# ssr_ansteuerung_v7.net
KiCad netlist of a schematic drawn in EAGLE
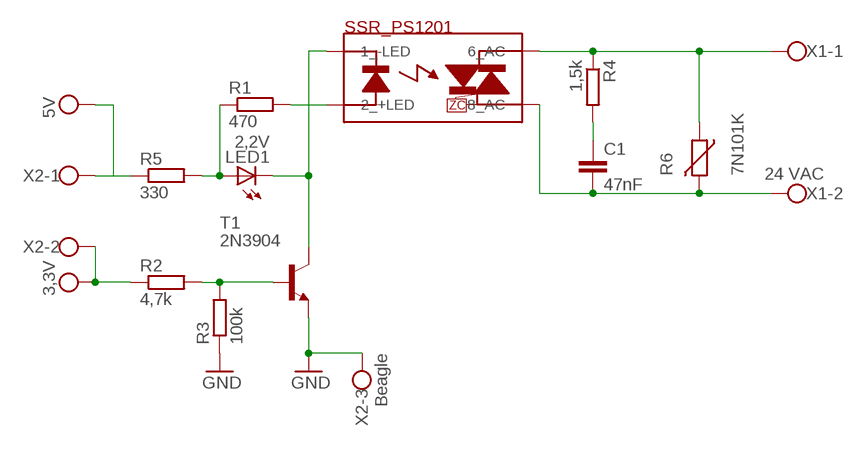
[diagram p0: schematic, sheet 1]

(export (version "E")
  (design (tool "Eeschema 10.0.6"))
  (components
    (comp (ref "C1")
      (value "47nF")
      (footprint "eagle-import:C7.5B3")
      (libsource (lib "eagle-import") (part "C7.5/3"))
    )
    (comp (ref "LED1")
      (value "2,2V")
      (footprint "eagle-import:LED5MM")
      (libsource (lib "eagle-import") (part "LED5MM"))
    )
    (comp (ref "R1")
      (value "470")
      (footprint "eagle-import:0204_7")
      (libsource (lib "eagle-import") (part "R-EU_0204/7"))
    )
    (comp (ref "R2")
      (value "4,7k")
      (footprint "eagle-import:0204_7")
      (libsource (lib "eagle-import") (part "R-EU_0204/7"))
    )
    (comp (ref "R3")
      (value "100k")
      (footprint "eagle-import:0204_7")
      (libsource (lib "eagle-import") (part "R-EU_0204/7"))
    )
    (comp (ref "R4")
      (value "1,5k")
      (footprint "eagle-import:0204_7")
      (libsource (lib "eagle-import") (part "R-EU_0204/7"))
    )
    (comp (ref "R5")
      (value "330")
      (footprint "eagle-import:0204_7")
      (libsource (lib "eagle-import") (part "R-EU_0204/7"))
    )
    (comp (ref "R6")
      (value "7N101K")
      (footprint "eagle-import:R-5")
      (libsource (lib "eagle-import") (part "VARISTOR-5"))
    )
    (comp (ref "SSR_PS1201")
      (value "SSR PS1201")
      (footprint "eagle-import:S202S02")
      (libsource (lib "eagle-import") (part "IXYS_PS1201_SSRSIP4/8"))
    )
    (comp (ref "T1")
      (value "2N3904")
      (footprint "eagle-import:TO92")
      (libsource (lib "eagle-import") (part "2N3904"))
    )
    (comp (ref "X1")
      (value "24 VAC")
      (footprint "eagle-import:W237-102")
      (fields (field (name "MPN") "237-102"))
      (libsource (lib "eagle-import") (part "W237-102"))
    )
    (comp (ref "X2")
      (value "Beagle")
      (footprint "eagle-import:W237-103")
      (fields (field (name "MPN") "237-103"))
      (libsource (lib "eagle-import") (part "W237-103"))
    )
  )
  (nets
    (net (code "1") (name "3,3V") (class "Default")
      (node (ref "R2") (pin "1") (pinfunction "1_1") (pintype "passive"))
      (node (ref "X2") (pin "2") (pinfunction "KL_2") (pintype "passive"))
    )
    (net (code "2") (name "GND") (class "Default")
      (node (ref "R3") (pin "1") (pinfunction "1_1") (pintype "passive"))
      (node (ref "T1") (pin "3") (pinfunction "E_3") (pintype "passive"))
      (node (ref "X2") (pin "3") (pinfunction "KL_3") (pintype "passive"))
    )
    (net (code "3") (name "Net-(C1-Pad1)") (class "Default")
      (node (ref "C1") (pin "1") (pinfunction "1_1") (pintype "passive"))
      (node (ref "R4") (pin "2") (pinfunction "2_2") (pintype "passive"))
    )
    (net (code "4") (name "Net-(LED1-C)") (class "Default")
      (node (ref "LED1") (pin "K") (pinfunction "C_K") (pintype "passive"))
      (node (ref "SSR_PS1201") (pin "1") (pinfunction "1_-LED_1") (pintype "bidirectional"))
      (node (ref "T1") (pin "1") (pinfunction "C_1") (pintype "passive"))
    )
    (net (code "5") (name "Net-(LED1-PadA)") (class "Default")
      (node (ref "LED1") (pin "A") (pinfunction "A_A") (pintype "passive"))
      (node (ref "R1") (pin "1") (pinfunction "1_1") (pintype "passive"))
      (node (ref "R5") (pin "2") (pinfunction "2_2") (pintype "passive"))
    )
    (net (code "6") (name "Net-(SSR_PS1201-2_+LED)") (class "Default")
      (node (ref "R1") (pin "2") (pinfunction "2_2") (pintype "passive"))
      (node (ref "SSR_PS1201") (pin "2") (pinfunction "2_+LED_2") (pintype "bidirectional"))
    )
    (net (code "7") (name "Net-(SSR_PS1201-6_AC)") (class "Default")
      (node (ref "R4") (pin "1") (pinfunction "1_1") (pintype "passive"))
      (node (ref "R6") (pin "1") (pinfunction "1_1") (pintype "passive"))
      (node (ref "SSR_PS1201") (pin "6") (pinfunction "6_AC_6") (pintype "bidirectional"))
      (node (ref "X1") (pin "1") (pinfunction "KL_1") (pintype "passive"))
    )
    (net (code "8") (name "Net-(SSR_PS1201-8_AC)") (class "Default")
      (node (ref "C1") (pin "2") (pinfunction "2_2") (pintype "passive"))
      (node (ref "R6") (pin "2") (pinfunction "2_2") (pintype "passive"))
      (node (ref "SSR_PS1201") (pin "8") (pinfunction "8_AC_8") (pintype "bidirectional"))
      (node (ref "X1") (pin "2") (pinfunction "KL_2") (pintype "passive"))
    )
    (net (code "9") (name "Net-(T1-B)") (class "Default")
      (node (ref "R2") (pin "2") (pinfunction "2_2") (pintype "passive"))
      (node (ref "R3") (pin "2") (pinfunction "2_2") (pintype "passive"))
      (node (ref "T1") (pin "2") (pinfunction "B_2") (pintype "passive"))
    )
    (net (code "10") (name "Net-(X2A-KL)") (class "Default")
      (node (ref "R5") (pin "1") (pinfunction "1_1") (pintype "passive"))
      (node (ref "X2") (pin "1") (pinfunction "KL_1") (pintype "passive"))
    )
  )
)
